# Zumo-Feather-1_0.net
KiCad netlist of a schematic drawn in EAGLE
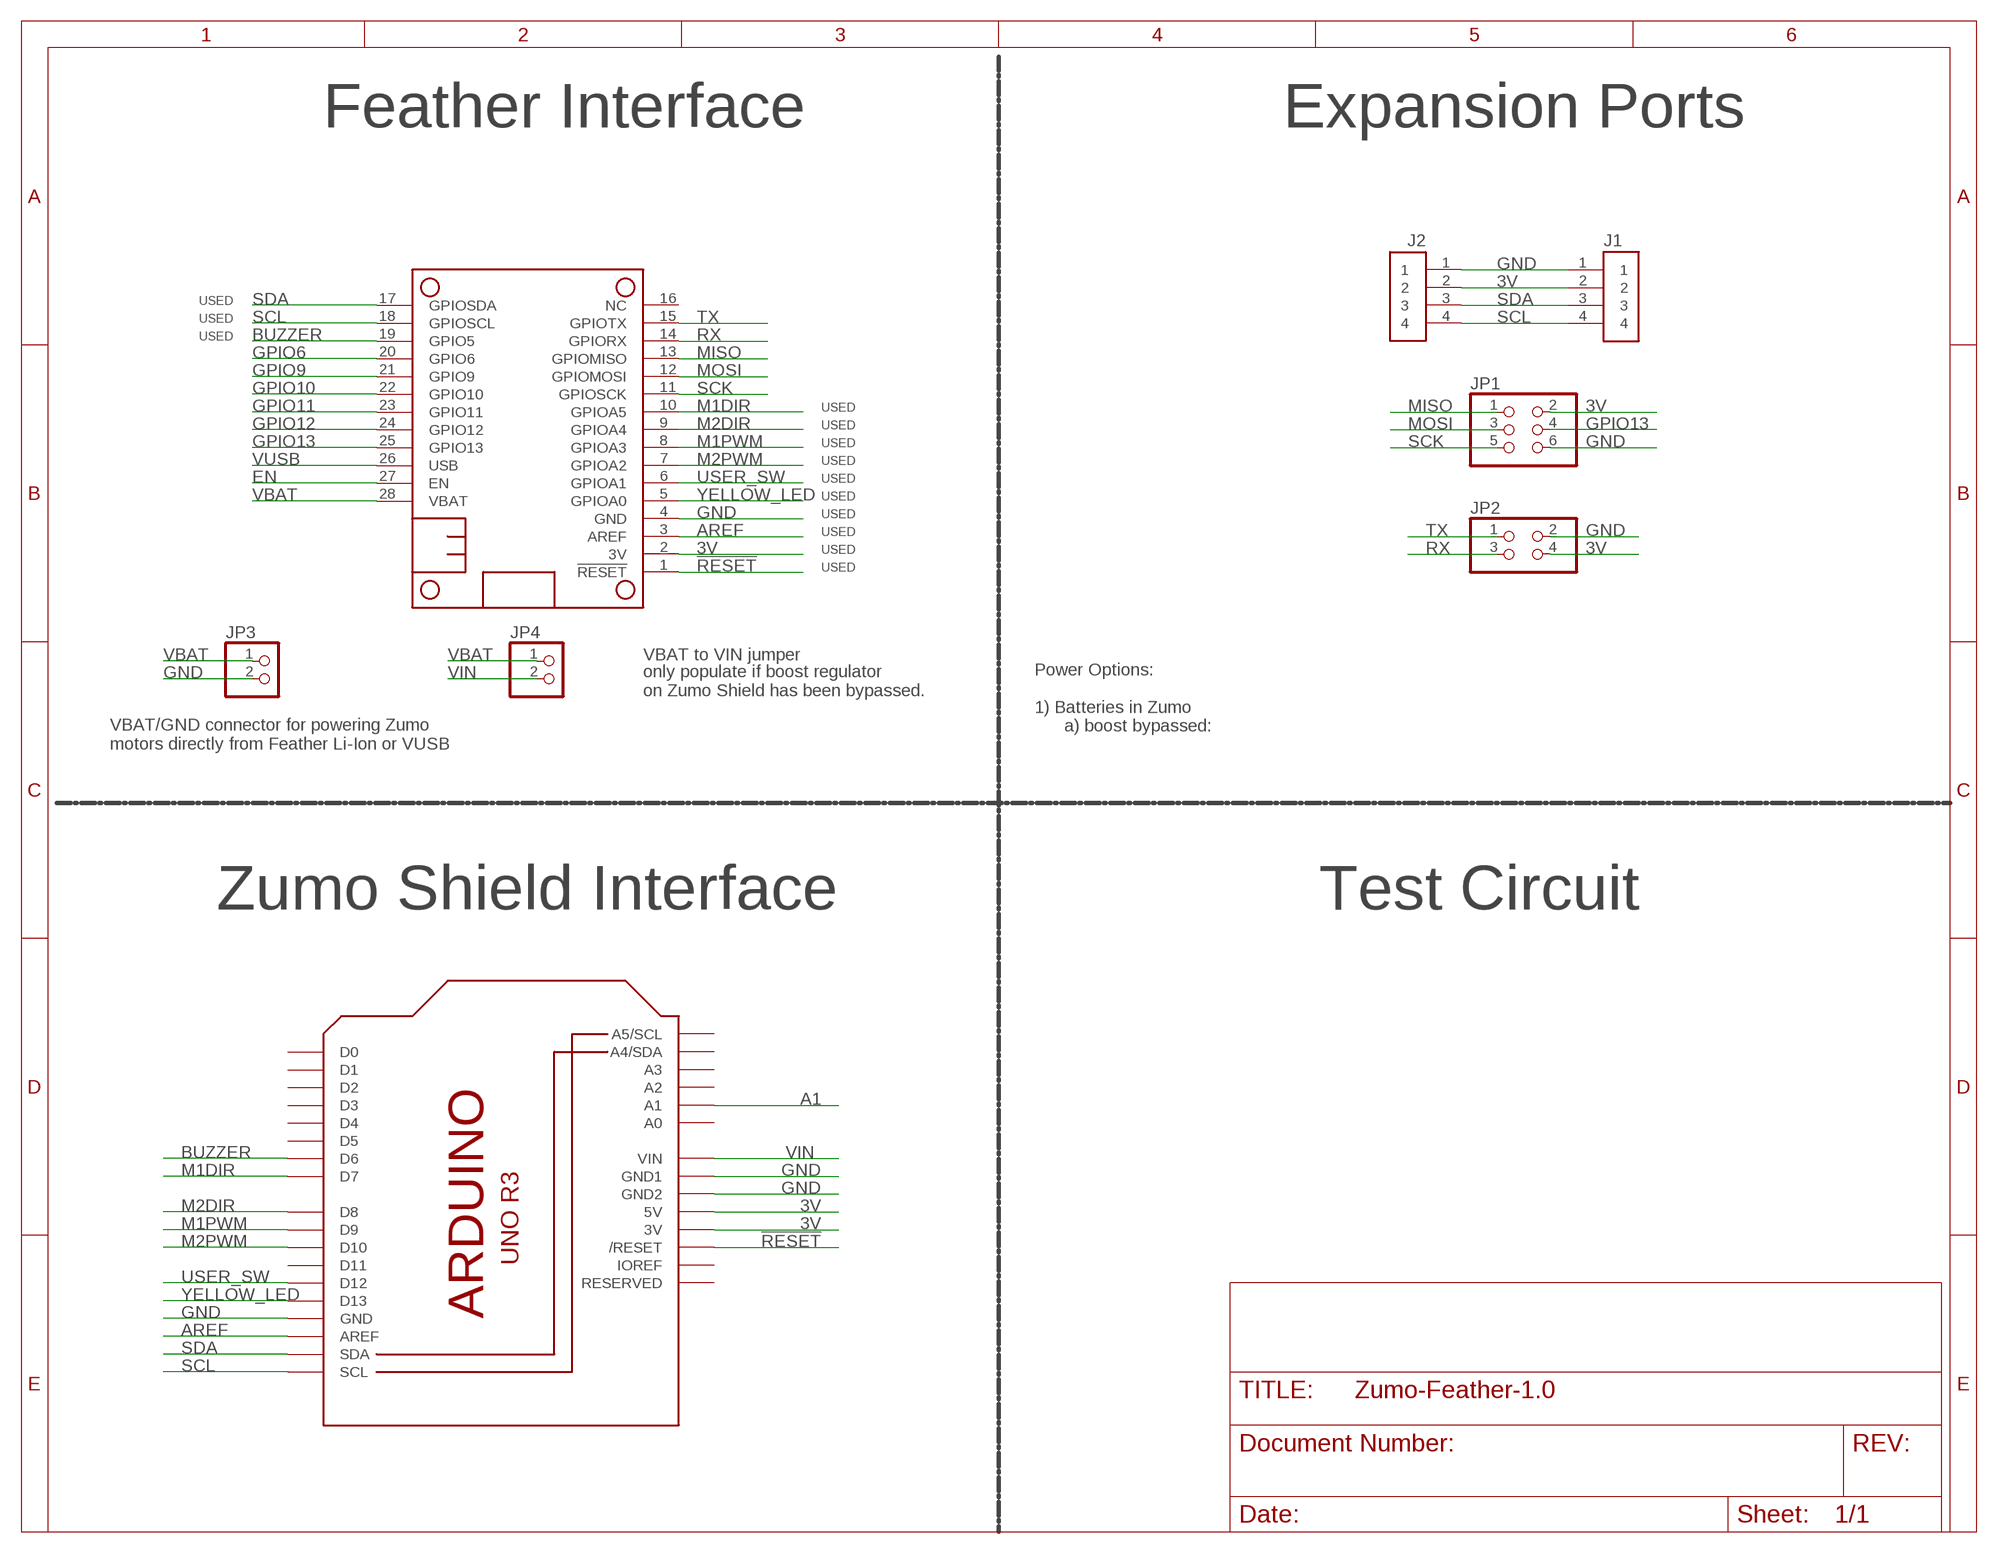
[diagram p0: schematic, sheet 1]

(export (version "E")
  (design (tool "Eeschema 10.0.6"))
  (components
    (comp (ref "J1")
      (value "CON-SM04B-SRSS-TB")
      (footprint "eagle-import:JST_SH_4X1")
      (fields
        (field (name "MANUFACTURER") "JST Sales America Inc.")
        (field (name "PART_NUMBER") "SM04B-SRSS-TB")
        (field (name "TOLERANCE") "NA")
      )
      (libsource (lib "eagle-import") (part "CON-SM04B-SRSS-TB"))
    )
    (comp (ref "J2")
      (value "CON-SM04B-SRSS-TB")
      (footprint "eagle-import:JST_SH_4X1")
      (fields
        (field (name "MANUFACTURER") "JST Sales America Inc.")
        (field (name "PART_NUMBER") "SM04B-SRSS-TB")
        (field (name "TOLERANCE") "NA")
      )
      (libsource (lib "eagle-import") (part "CON-SM04B-SRSS-TB"))
    )
    (comp (ref "JP1")
      (value "PINHD-2X3")
      (footprint "eagle-import:2X03")
      (libsource (lib "eagle-import") (part "PINHD-2X3"))
    )
    (comp (ref "JP2")
      (value "PINHD-2X2")
      (footprint "eagle-import:2X02")
      (libsource (lib "eagle-import") (part "PINHD-2X2"))
    )
    (comp (ref "JP3")
      (value "PINHD-1X2")
      (footprint "eagle-import:1X02")
      (libsource (lib "eagle-import") (part "PINHD-1X2"))
    )
    (comp (ref "JP4")
      (value "PINHD-1X2")
      (footprint "eagle-import:1X02")
      (libsource (lib "eagle-import") (part "PINHD-1X2"))
    )
    (comp (ref "MS1")
      (value "BRD-FEATHERWING_NODIM_NOMNT")
      (footprint "eagle-import:FEATHERWING_DIM_MNT")
      (libsource (lib "eagle-import") (part "BRD-FEATHERWING_NODIM_NOMNT"))
    )
    (comp (ref "U1")
      (value "BRD-ARDUINOR3-DIMENSION")
      (footprint "eagle-import:ARDUINOR3")
      (libsource (lib "eagle-import") (part "BRD-ARDUINOR3-DIMENSION"))
    )
  )
  (nets
    (net (code "1") (name "/3V") (class "Default")
      (node (ref "J1") (pin "2") (pinfunction "2_2") (pintype "bidirectional"))
      (node (ref "J2") (pin "2") (pinfunction "2_2") (pintype "bidirectional"))
      (node (ref "JP1") (pin "2") (pinfunction "2_2") (pintype "passive"))
      (node (ref "JP2") (pin "4") (pinfunction "4_4") (pintype "passive"))
      (node (ref "MS1") (pin "2") (pinfunction "3V_2") (pintype "power_in"))
      (node (ref "U1") (pin "3V") (pinfunction "3V_3V") (pintype "power_in"))
      (node (ref "U1") (pin "5V") (pinfunction "5V_5V") (pintype "power_in"))
    )
    (net (code "2") (name "/A1") (class "Default")
      (node (ref "U1") (pin "A1") (pinfunction "A1_A1") (pintype "bidirectional"))
    )
    (net (code "3") (name "/AREF") (class "Default")
      (node (ref "MS1") (pin "3") (pinfunction "AREF_3") (pintype "passive"))
      (node (ref "U1") (pin "AREF") (pinfunction "AREF_AREF") (pintype "bidirectional"))
    )
    (net (code "4") (name "/BUZZER") (class "Default")
      (node (ref "MS1") (pin "19") (pinfunction "GPIO5_19") (pintype "bidirectional"))
      (node (ref "U1") (pin "D6") (pinfunction "D6_D6") (pintype "bidirectional"))
    )
    (net (code "5") (name "/EN") (class "Default")
      (node (ref "MS1") (pin "27") (pinfunction "EN_27") (pintype "passive"))
    )
    (net (code "6") (name "/GND") (class "Default")
      (node (ref "J1") (pin "1") (pinfunction "1_1") (pintype "bidirectional"))
      (node (ref "J2") (pin "1") (pinfunction "1_1") (pintype "bidirectional"))
      (node (ref "JP1") (pin "6") (pinfunction "6_6") (pintype "passive"))
      (node (ref "JP2") (pin "2") (pinfunction "2_2") (pintype "passive"))
      (node (ref "JP3") (pin "2") (pinfunction "2_2") (pintype "passive"))
      (node (ref "MS1") (pin "4") (pinfunction "GND_4") (pintype "power_in"))
      (node (ref "U1") (pin "GND") (pinfunction "GND_GND") (pintype "power_in"))
      (node (ref "U1") (pin "GND1") (pinfunction "GND1_GND1") (pintype "power_in"))
      (node (ref "U1") (pin "GND2") (pinfunction "GND2_GND2") (pintype "power_in"))
    )
    (net (code "7") (name "/GPIO6") (class "Default")
      (node (ref "MS1") (pin "20") (pinfunction "GPIO6_20") (pintype "bidirectional"))
    )
    (net (code "8") (name "/GPIO9") (class "Default")
      (node (ref "MS1") (pin "21") (pinfunction "GPIO9_21") (pintype "bidirectional"))
    )
    (net (code "9") (name "/GPIO10") (class "Default")
      (node (ref "MS1") (pin "22") (pinfunction "GPIO10_22") (pintype "bidirectional"))
    )
    (net (code "10") (name "/GPIO11") (class "Default")
      (node (ref "MS1") (pin "23") (pinfunction "GPIO11_23") (pintype "bidirectional"))
    )
    (net (code "11") (name "/GPIO12") (class "Default")
      (node (ref "MS1") (pin "24") (pinfunction "GPIO12_24") (pintype "bidirectional"))
    )
    (net (code "12") (name "/GPIO13") (class "Default")
      (node (ref "JP1") (pin "4") (pinfunction "4_4") (pintype "passive"))
      (node (ref "MS1") (pin "25") (pinfunction "GPIO13_25") (pintype "bidirectional"))
    )
    (net (code "13") (name "/M1DIR") (class "Default")
      (node (ref "MS1") (pin "10") (pinfunction "GPIOA5_10") (pintype "bidirectional"))
      (node (ref "U1") (pin "D7") (pinfunction "D7_D7") (pintype "bidirectional"))
    )
    (net (code "14") (name "/M1PWM") (class "Default")
      (node (ref "MS1") (pin "8") (pinfunction "GPIOA3_8") (pintype "bidirectional"))
      (node (ref "U1") (pin "D9") (pinfunction "D9_D9") (pintype "bidirectional"))
    )
    (net (code "15") (name "/M2DIR") (class "Default")
      (node (ref "MS1") (pin "9") (pinfunction "GPIOA4_9") (pintype "bidirectional"))
      (node (ref "U1") (pin "D8") (pinfunction "D8_D8") (pintype "bidirectional"))
    )
    (net (code "16") (name "/M2PWM") (class "Default")
      (node (ref "MS1") (pin "7") (pinfunction "GPIOA2_7") (pintype "bidirectional"))
      (node (ref "U1") (pin "D10") (pinfunction "D10_D10") (pintype "bidirectional"))
    )
    (net (code "17") (name "/MISO") (class "Default")
      (node (ref "JP1") (pin "1") (pinfunction "1_1") (pintype "passive"))
      (node (ref "MS1") (pin "13") (pinfunction "GPIOMISO_13") (pintype "bidirectional"))
    )
    (net (code "18") (name "/MOSI") (class "Default")
      (node (ref "JP1") (pin "3") (pinfunction "3_3") (pintype "passive"))
      (node (ref "MS1") (pin "12") (pinfunction "GPIOMOSI_12") (pintype "bidirectional"))
    )
    (net (code "19") (name "/RX") (class "Default")
      (node (ref "JP2") (pin "3") (pinfunction "3_3") (pintype "passive"))
      (node (ref "MS1") (pin "14") (pinfunction "GPIORX_14") (pintype "bidirectional"))
    )
    (net (code "20") (name "/SCK") (class "Default")
      (node (ref "JP1") (pin "5") (pinfunction "5_5") (pintype "passive"))
      (node (ref "MS1") (pin "11") (pinfunction "GPIOSCK_11") (pintype "bidirectional"))
    )
    (net (code "21") (name "/SCL") (class "Default")
      (node (ref "J1") (pin "4") (pinfunction "4_4") (pintype "bidirectional"))
      (node (ref "J2") (pin "4") (pinfunction "4_4") (pintype "bidirectional"))
      (node (ref "MS1") (pin "18") (pinfunction "GPIOSCL_18") (pintype "bidirectional"))
      (node (ref "U1") (pin "SCL") (pinfunction "SCL_SCL") (pintype "bidirectional"))
    )
    (net (code "22") (name "/SDA") (class "Default")
      (node (ref "J1") (pin "3") (pinfunction "3_3") (pintype "bidirectional"))
      (node (ref "J2") (pin "3") (pinfunction "3_3") (pintype "bidirectional"))
      (node (ref "MS1") (pin "17") (pinfunction "GPIOSDA_17") (pintype "bidirectional"))
      (node (ref "U1") (pin "SDA") (pinfunction "SDA_SDA") (pintype "bidirectional"))
    )
    (net (code "23") (name "/TX") (class "Default")
      (node (ref "JP2") (pin "1") (pinfunction "1_1") (pintype "passive"))
      (node (ref "MS1") (pin "15") (pinfunction "GPIOTX_15") (pintype "bidirectional"))
    )
    (net (code "24") (name "/USER_SW") (class "Default")
      (node (ref "MS1") (pin "6") (pinfunction "GPIOA1_6") (pintype "bidirectional"))
      (node (ref "U1") (pin "D12") (pinfunction "D12_D12") (pintype "bidirectional"))
    )
    (net (code "25") (name "/VBAT") (class "Default")
      (node (ref "JP3") (pin "1") (pinfunction "1_1") (pintype "passive"))
      (node (ref "JP4") (pin "1") (pinfunction "1_1") (pintype "passive"))
      (node (ref "MS1") (pin "28") (pinfunction "VBAT_28") (pintype "power_in"))
    )
    (net (code "26") (name "/VIN") (class "Default")
      (node (ref "JP4") (pin "2") (pinfunction "2_2") (pintype "passive"))
      (node (ref "U1") (pin "VIN") (pinfunction "VIN_VIN") (pintype "power_in"))
    )
    (net (code "27") (name "/VUSB") (class "Default")
      (node (ref "MS1") (pin "26") (pinfunction "USB_26") (pintype "power_in"))
    )
    (net (code "28") (name "/YELLOW_LED") (class "Default")
      (node (ref "MS1") (pin "5") (pinfunction "GPIOA0_5") (pintype "bidirectional"))
      (node (ref "U1") (pin "D13") (pinfunction "D13_D13") (pintype "bidirectional"))
    )
    (net (code "29") (name "/~{RESET}") (class "Default")
      (node (ref "MS1") (pin "1") (pinfunction "~{RESET}_1") (pintype "input"))
      (node (ref "U1") (pin "RESET") (pinfunction "/RESET_RESET") (pintype "bidirectional"))
    )
    (net (code "30") (name "unconnected-(MS1-NC-Pad16)") (class "Default")
      (node (ref "MS1") (pin "16") (pinfunction "NC_16") (pintype "passive"))
    )
    (net (code "31") (name "unconnected-(U1-A4{slash}SDA-PadA4)") (class "Default")
      (node (ref "U1") (pin "A4") (pinfunction "A4/SDA_A4") (pintype "bidirectional"))
    )
    (net (code "32") (name "unconnected-(U1-A5{slash}SCL-PadA5)") (class "Default")
      (node (ref "U1") (pin "A5") (pinfunction "A5/SCL_A5") (pintype "bidirectional"))
    )
    (net (code "33") (name "unconnected-(U1-PadA0)") (class "Default")
      (node (ref "U1") (pin "A0") (pinfunction "A0_A0") (pintype "bidirectional"))
    )
    (net (code "34") (name "unconnected-(U1-PadA2)") (class "Default")
      (node (ref "U1") (pin "A2") (pinfunction "A2_A2") (pintype "bidirectional"))
    )
    (net (code "35") (name "unconnected-(U1-PadA3)") (class "Default")
      (node (ref "U1") (pin "A3") (pinfunction "A3_A3") (pintype "bidirectional"))
    )
    (net (code "36") (name "unconnected-(U1-PadD0)") (class "Default")
      (node (ref "U1") (pin "D0") (pinfunction "D0_D0") (pintype "bidirectional"))
    )
    (net (code "37") (name "unconnected-(U1-PadD1)") (class "Default")
      (node (ref "U1") (pin "D1") (pinfunction "D1_D1") (pintype "bidirectional"))
    )
    (net (code "38") (name "unconnected-(U1-PadD2)") (class "Default")
      (node (ref "U1") (pin "D2") (pinfunction "D2_D2") (pintype "bidirectional"))
    )
    (net (code "39") (name "unconnected-(U1-PadD3)") (class "Default")
      (node (ref "U1") (pin "D3") (pinfunction "D3_D3") (pintype "bidirectional"))
    )
    (net (code "40") (name "unconnected-(U1-PadD4)") (class "Default")
      (node (ref "U1") (pin "D4") (pinfunction "D4_D4") (pintype "bidirectional"))
    )
    (net (code "41") (name "unconnected-(U1-PadD5)") (class "Default")
      (node (ref "U1") (pin "D5") (pinfunction "D5_D5") (pintype "bidirectional"))
    )
    (net (code "42") (name "unconnected-(U1-PadD11)") (class "Default")
      (node (ref "U1") (pin "D11") (pinfunction "D11_D11") (pintype "bidirectional"))
    )
    (net (code "43") (name "unconnected-(U1-PadIOREF)") (class "Default")
      (node (ref "U1") (pin "IOREF") (pinfunction "IOREF_IOREF") (pintype "output"))
    )
    (net (code "44") (name "unconnected-(U1-PadRESERVED)") (class "Default")
      (node (ref "U1") (pin "RESERVED") (pinfunction "RESERVED_RESERVED") (pintype "no_connect"))
    )
  )
)
